# PA-15-30W.net
KiCad netlist of a schematic drawn in Altium Designer
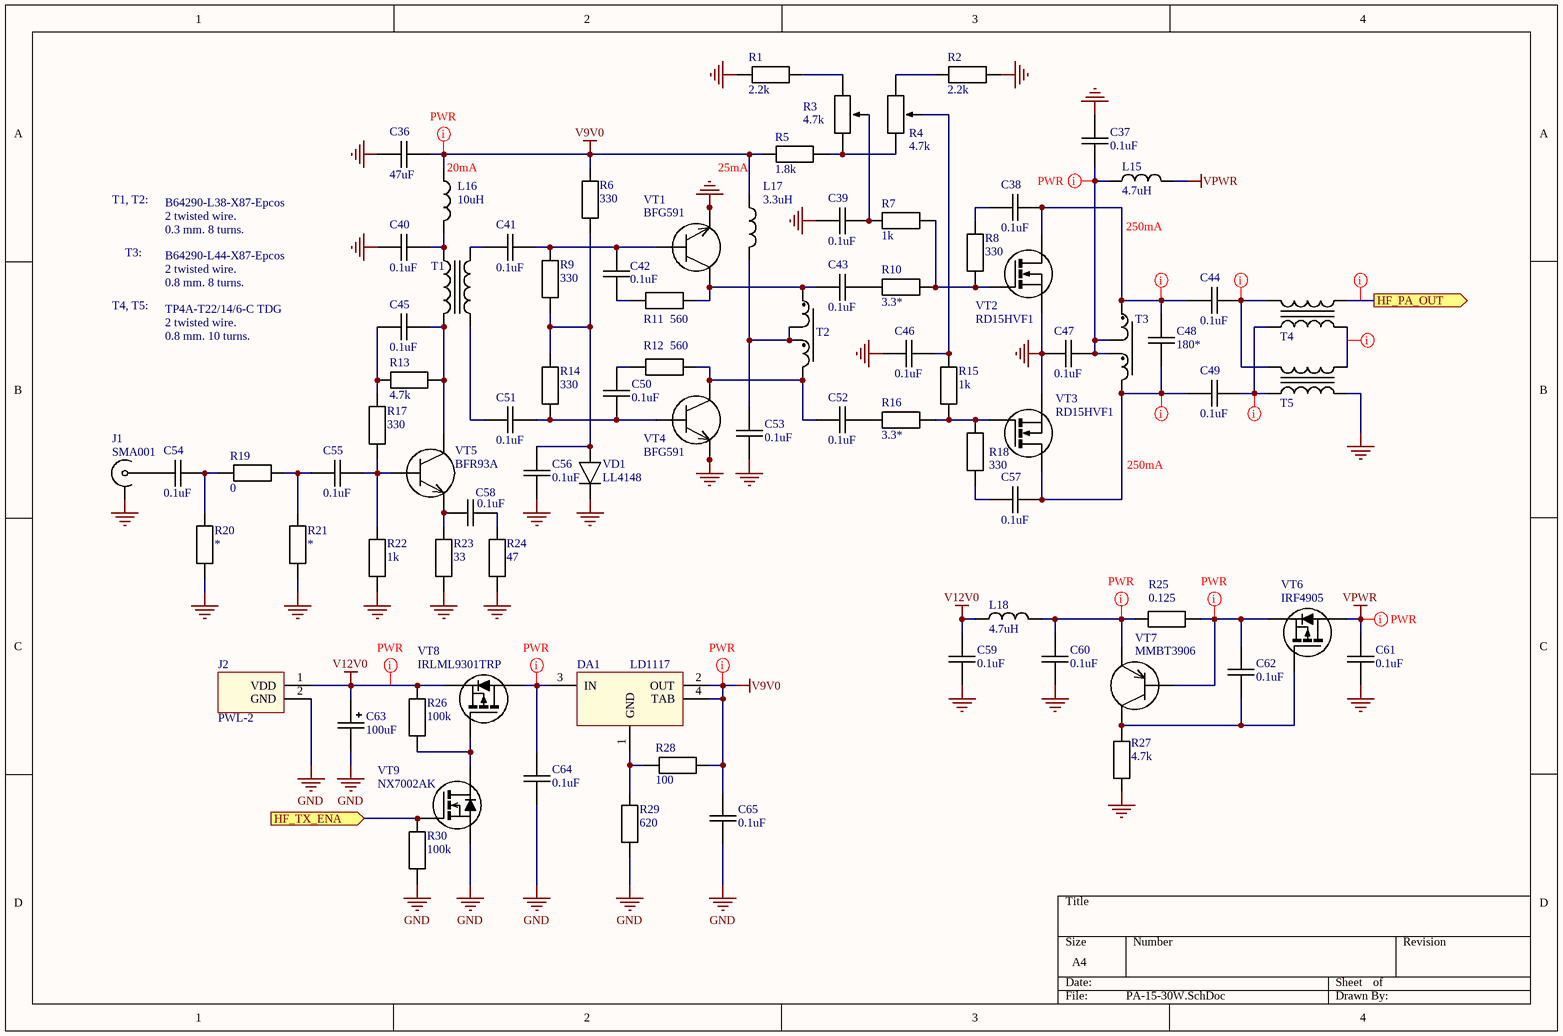
[diagram p0: PA-15-30W.SchDoc]

(export (version "E")
  (design (tool "Eeschema 10.0.6"))
  (components
    (comp (ref "C36")
      (value "47uF")
      (footprint "CAPC3225X270N")
      (description "GRM32ER71A476KE15L")
      (libsource (lib "common-lib") (part "Cap1210"))
    )
    (comp (ref "C37")
      (value "0.1uF")
      (footprint "CAPC3216X125N")
      (description "FM31X104K251EEG")
      (libsource (lib "common-lib") (part "Cap1206"))
    )
    (comp (ref "C38")
      (value "0.1uF")
      (footprint "CAPC2013X100N")
      (description "Capacitor 2x1.25 mm")
      (libsource (lib "common-lib") (part "Cap0805"))
    )
    (comp (ref "C39")
      (value "0.1uF")
      (footprint "CAPC2013X100N")
      (description "Capacitor 2x1.25 mm")
      (libsource (lib "common-lib") (part "Cap0805"))
    )
    (comp (ref "C40")
      (value "0.1uF")
      (footprint "CAPC2013X100N")
      (description "Capacitor 2x1.25 mm")
      (libsource (lib "common-lib") (part "Cap0805"))
    )
    (comp (ref "C41")
      (value "0.1uF")
      (footprint "CAPC2013X100N")
      (description "Capacitor 2x1.25 mm")
      (libsource (lib "common-lib") (part "Cap0805"))
    )
    (comp (ref "C42")
      (value "0.1uF")
      (footprint "CAPC2013X100N")
      (description "Capacitor 2x1.25 mm")
      (libsource (lib "common-lib") (part "Cap0805"))
    )
    (comp (ref "C43")
      (value "0.1uF")
      (footprint "CAPC2013X100N")
      (description "Capacitor 2x1.25 mm")
      (libsource (lib "common-lib") (part "Cap0805"))
    )
    (comp (ref "C44")
      (value "0.1uF")
      (footprint "CAPC4532X218N")
      (description "GRM43DR72J104KW01 (1812, X7R:EIA, 0.1uF, DC630V), rcs")
      (libsource (lib "common-lib") (part "Cap1812"))
    )
    (comp (ref "C45")
      (value "0.1uF")
      (footprint "CAPC2013X100N")
      (description "Capacitor 2x1.25 mm")
      (libsource (lib "common-lib") (part "Cap0805"))
    )
    (comp (ref "C46")
      (value "0.1uF")
      (footprint "CAPC2013X100N")
      (description "Capacitor 2x1.25 mm")
      (libsource (lib "common-lib") (part "Cap0805"))
    )
    (comp (ref "C47")
      (value "0.1uF")
      (footprint "CAPC3216X125N")
      (description "FM31X104K251EEG, rcs")
      (libsource (lib "common-lib") (part "Cap1206"))
    )
    (comp (ref "C48")
      (value "180*")
      (footprint "CAPC3216X125N")
      (description "1206, NP0, 1kV")
      (libsource (lib "common-lib") (part "Cap1206"))
    )
    (comp (ref "C49")
      (value "0.1uF")
      (footprint "CAPC4532X218N")
      (description "GRM43DR72J104KW01 (1812, X7R:EIA, 0.1uF, DC630V), rcs")
      (libsource (lib "common-lib") (part "Cap1812"))
    )
    (comp (ref "C50")
      (value "0.1uF")
      (footprint "CAPC2013X100N")
      (description "Capacitor 2x1.25 mm")
      (libsource (lib "common-lib") (part "Cap0805"))
    )
    (comp (ref "C51")
      (value "0.1uF")
      (footprint "CAPC2013X100N")
      (description "Capacitor 2x1.25 mm")
      (libsource (lib "common-lib") (part "Cap0805"))
    )
    (comp (ref "C52")
      (value "0.1uF")
      (footprint "CAPC2013X100N")
      (description "Capacitor 2x1.25 mm")
      (libsource (lib "common-lib") (part "Cap0805"))
    )
    (comp (ref "C53")
      (value "0.1uF")
      (footprint "CAPC2013X100N")
      (description "Capacitor 2x1.25 mm")
      (libsource (lib "common-lib") (part "Cap0805"))
    )
    (comp (ref "C54")
      (value "0.1uF")
      (footprint "CAPC2013X100N")
      (description "Capacitor 2x1.25 mm")
      (libsource (lib "common-lib") (part "Cap0805"))
    )
    (comp (ref "C55")
      (value "0.1uF")
      (footprint "CAPC2013X100N")
      (description "Capacitor 2x1.25 mm")
      (libsource (lib "common-lib") (part "Cap0805"))
    )
    (comp (ref "C56")
      (value "0.1uF")
      (footprint "CAPC2013X100N")
      (description "Capacitor 2x1.25 mm")
      (libsource (lib "common-lib") (part "Cap0805"))
    )
    (comp (ref "C57")
      (value "0.1uF")
      (footprint "CAPC2013X100N")
      (description "Capacitor 2x1.25 mm")
      (libsource (lib "common-lib") (part "Cap0805"))
    )
    (comp (ref "C58")
      (value "0.1uF")
      (footprint "CAPC2013X100N")
      (description "Capacitor 2x1.25 mm")
      (libsource (lib "common-lib") (part "Cap0805"))
    )
    (comp (ref "C59")
      (value "0.1uF")
      (footprint "CAPC2013X100N")
      (description "Capacitor 2x1.25 mm")
      (libsource (lib "common-lib") (part "Cap0805"))
    )
    (comp (ref "C60")
      (value "0.1uF")
      (footprint "CAPC2013X100N")
      (description "Capacitor 2x1.25 mm")
      (libsource (lib "common-lib") (part "Cap0805"))
    )
    (comp (ref "C61")
      (value "0.1uF")
      (footprint "CAPC2013X100N")
      (description "Capacitor 2x1.25 mm")
      (libsource (lib "common-lib") (part "Cap0805"))
    )
    (comp (ref "C62")
      (value "0.1uF")
      (footprint "CAPC2013X100N")
      (description "Capacitor 2x1.25 mm")
      (libsource (lib "common-lib") (part "Cap0805"))
    )
    (comp (ref "C63")
      (value "100uF")
      (footprint "CAPPR500-1050X1300")
      (description "EEUFR1E471, imrad")
      (libsource (lib "common-lib") (part "CapPolarized"))
    )
    (comp (ref "C64")
      (value "0.1uF")
      (footprint "CAPC2013X100N")
      (description "Capacitor 2x1.25 mm")
      (libsource (lib "common-lib") (part "Cap0805"))
    )
    (comp (ref "C65")
      (value "0.1uF")
      (footprint "CAPC2013X100N")
      (description "Capacitor 2x1.25 mm")
      (libsource (lib "common-lib") (part "Cap0805"))
    )
    (comp (ref "DA1")
      (value "LD1117")
      (footprint "SOT230P700X180-4N")
      (description "Adjustable and fixed low drop positive voltage regulator")
      (libsource (lib "PALib") (part "LD1117"))
    )
    (comp (ref "J1") (value "SMA001") (footprint "SMA002") (libsource (lib "PALib") (part "RF Connector")))
    (comp (ref "J2")
      (value "PWL-2")
      (footprint "PWL-2")
      (libsource (lib "common-lib") (part "PWR_CONNECTOR"))
    )
    (comp (ref "L15")
      (value "4.7uH")
      (footprint "Inductor radial")
      (description "Bochen, 4.7µH±10%, Idc=5.0А, Rdc мax=0.05")
      (libsource (lib "PALib") (part "Inductor"))
    )
    (comp (ref "L16")
      (value "10uH")
      (footprint "RESC2013X64N")
      (description "SMD 0805 50-100mA\r\nLQM21FN100M70L, Imrad")
      (libsource (lib "") (part "Inductor_1"))
    )
    (comp (ref "L17")
      (value "3.3uH")
      (footprint "RES1270-650X250")
      (description "3,3uH ±10% аксиальный дроссель 670mA 0,34Ohm (KLS18-EC36-3R3K-A – KLS)")
      (libsource (lib "") (part "Inductor_1"))
    )
    (comp (ref "L18")
      (value "4.7uH")
      (footprint "Inductor radial")
      (description "Bochen, 4.7µH±10%, Idc=5.0А, Rdc мax=0.05")
      (libsource (lib "PALib") (part "Inductor"))
    )
    (comp (ref "R1")
      (value "2.2k")
      (footprint "RESC2013X64N")
      (libsource (lib "common-lib") (part "Res0805"))
    )
    (comp (ref "R2")
      (value "2.2k")
      (footprint "RESC2013X64N")
      (libsource (lib "common-lib") (part "Res0805"))
    )
    (comp (ref "R3")
      (value "4.7k")
      (footprint "3296W")
      (description "4,7 kOhm 3296W (KLS4-3296W-472), rcs")
      (libsource (lib "PALib") (part "potentiometer"))
    )
    (comp (ref "R4") (value "4.7k") (footprint "3296W") (libsource (lib "PALib") (part "potentiometer")))
    (comp (ref "R5")
      (value "1.8k")
      (footprint "RESC2013X64N")
      (libsource (lib "common-lib") (part "Res0805"))
    )
    (comp (ref "R6") (value "330") (footprint "RESC2013X64N") (libsource (lib "common-lib") (part "Res0805")))
    (comp (ref "R7") (value "1k") (footprint "RESC2013X64N") (libsource (lib "common-lib") (part "Res0805")))
    (comp (ref "R8") (value "330") (footprint "RESC2013X64N") (libsource (lib "common-lib") (part "Res0805")))
    (comp (ref "R9") (value "330") (footprint "RESC2013X64N") (libsource (lib "common-lib") (part "Res0805")))
    (comp (ref "R10")
      (value "3.3*")
      (footprint "RESC2013X64N")
      (libsource (lib "common-lib") (part "Res0805"))
    )
    (comp (ref "R11")
      (value "560")
      (footprint "RESC2013X64N")
      (libsource (lib "common-lib") (part "Res0805"))
    )
    (comp (ref "R12")
      (value "560")
      (footprint "RESC2013X64N")
      (libsource (lib "common-lib") (part "Res0805"))
    )
    (comp (ref "R13")
      (value "4.7k")
      (footprint "RESC2013X64N")
      (libsource (lib "common-lib") (part "Res0805"))
    )
    (comp (ref "R14")
      (value "330")
      (footprint "RESC2013X64N")
      (libsource (lib "common-lib") (part "Res0805"))
    )
    (comp (ref "R15") (value "1k") (footprint "RESC2013X64N") (libsource (lib "common-lib") (part "Res0805")))
    (comp (ref "R16")
      (value "3.3*")
      (footprint "RESC2013X64N")
      (libsource (lib "common-lib") (part "Res0805"))
    )
    (comp (ref "R17")
      (value "330")
      (footprint "RESC2013X64N")
      (libsource (lib "common-lib") (part "Res0805"))
    )
    (comp (ref "R18")
      (value "330")
      (footprint "RESC2013X64N")
      (libsource (lib "common-lib") (part "Res0805"))
    )
    (comp (ref "R19") (value "0") (footprint "RESC2013X64N") (libsource (lib "common-lib") (part "Res0805")))
    (comp (ref "R20") (value "*") (footprint "RESC2013X64N") (libsource (lib "common-lib") (part "Res0805")))
    (comp (ref "R21") (value "*") (footprint "RESC2013X64N") (libsource (lib "common-lib") (part "Res0805")))
    (comp (ref "R22") (value "1k") (footprint "RESC2013X64N") (libsource (lib "common-lib") (part "Res0805")))
    (comp (ref "R23") (value "33") (footprint "RESC2013X64N") (libsource (lib "common-lib") (part "Res0805")))
    (comp (ref "R24") (value "47") (footprint "RESC2013X64N") (libsource (lib "common-lib") (part "Res0805")))
    (comp (ref "R25")
      (value "0.125")
      (footprint "RESC3216X80N")
      (description "8 items 1 Om in paralel,1206")
      (libsource (lib "common-lib") (part "Res0805"))
    )
    (comp (ref "R26")
      (value "100k")
      (footprint "RESC2013X64N")
      (libsource (lib "common-lib") (part "Res0805"))
    )
    (comp (ref "R27")
      (value "4.7k")
      (footprint "RESC2013X64N")
      (libsource (lib "common-lib") (part "Res0805"))
    )
    (comp (ref "R28")
      (value "100")
      (footprint "RESC2013X64N")
      (libsource (lib "common-lib") (part "Res0805"))
    )
    (comp (ref "R29")
      (value "620")
      (footprint "RESC2013X64N")
      (libsource (lib "common-lib") (part "Res0805"))
    )
    (comp (ref "R30")
      (value "100k")
      (footprint "RESC2013X64N")
      (libsource (lib "common-lib") (part "Res0805"))
    )
    (comp (ref "T1")
      (value "R10*6*4 N87")
      (footprint "R10x6x4")
      (description "R10*6*4 N87 (В64290-L38-Х87-Epcos)")
      (libsource (lib "") (part "transformer type 2_1"))
    )
    (comp (ref "T2")
      (value "R10*6*4 N87")
      (footprint "R10x6x4")
      (description "R10*6*4 N87 (В64290-L38-Х87-Epcos)")
      (libsource (lib "PALib") (part "transformer type 1"))
    )
    (comp (ref "T3")
      (value "R12,5*7,5*5 N87")
      (footprint "R12.5x7.5x5")
      (description "R12,5*7,5*5 N87 (B64290-L44-X87-Epcos)")
      (libsource (lib "PALib") (part "transformer type 1"))
    )
    (comp (ref "T4")
      (value "TP4A-T22/14/6-C TDG")
      (footprint "R22x14x6")
      (libsource (lib "PALib") (part "transformer type 2"))
    )
    (comp (ref "T5")
      (value "TP4A-T22/14/6-C TDG")
      (footprint "R22x14x6")
      (libsource (lib "PALib") (part "transformer type 2"))
    )
    (comp (ref "VD1") (value "LL4148") (footprint "DIOMELF3515N") (libsource (lib "PALib") (part "DIODE")))
    (comp (ref "VT1")
      (value "BFG591")
      (footprint "SOT230P700X180-4N")
      (description "NPN 7 GHz wideband transistor")
      (libsource (lib "PALib") (part "BFG591"))
    )
    (comp (ref "VT2")
      (value "RD15HVF1")
      (footprint "TO-220-HFLIP")
      (libsource (lib "PALib") (part "RD15HVF1"))
    )
    (comp (ref "VT3") (value "RD15HVF1") (footprint "TO-220-HFLIP") (libsource (lib "") (part "RD15HVF1_1")))
    (comp (ref "VT4")
      (value "BFG591")
      (footprint "SOT230P700X180-4N")
      (description "NPN 7 GHz wideband transistor")
      (libsource (lib "PALib") (part "BFG591"))
    )
    (comp (ref "VT5")
      (value "BFR93A")
      (footprint "SOT95P229X119-3N")
      (description "NPN 6 GHz wideband transistor")
      (libsource (lib "PALib") (part "BFR93A"))
    )
    (comp (ref "VT6")
      (value "IRF4905")
      (footprint "TO-220-v")
      (description "HEXFET® Power MOSFET")
      (libsource (lib "PALib") (part "IRF4905"))
    )
    (comp (ref "VT7")
      (value "MMBT3906")
      (footprint "SOT95P229X119-3N")
      (description "MMBT3906LT1G, PNP General Purpose Amplifier\r\nimrad")
      (libsource (lib "PALib") (part "MMBT3906"))
    )
    (comp (ref "VT8")
      (value "IRLML9301TRP")
      (footprint "SOT95P229X119-3N")
      (libsource (lib "PALib") (part "IRLML9301TRP"))
    )
    (comp (ref "VT9")
      (value "NX7002AK")
      (footprint "SOT95P229X119-3N")
      (libsource (lib "common-lib") (part "N-MOSFET 1G 2S 3D"))
    )
  )
  (nets
    (net (code "1") (name "/HF_PA_OUT") (class "Default") (node (ref "T4") (pin "4") (pintype "passive")))
    (net (code "2") (name "/HF_TX_ENA") (class "Default")
      (node (ref "R30") (pin "2") (pintype "passive"))
      (node (ref "VT9") (pin "1") (pinfunction "G_1") (pintype "passive"))
    )
    (net (code "3") (name "GND") (class "Default")
      (node (ref "C36") (pin "1") (pintype "passive"))
      (node (ref "C37") (pin "2") (pintype "passive"))
      (node (ref "C39") (pin "2") (pintype "passive"))
      (node (ref "C40") (pin "2") (pintype "passive"))
      (node (ref "C46") (pin "1") (pintype "passive"))
      (node (ref "C47") (pin "1") (pintype "passive"))
      (node (ref "C53") (pin "2") (pintype "passive"))
      (node (ref "C56") (pin "2") (pintype "passive"))
      (node (ref "C59") (pin "2") (pintype "passive"))
      (node (ref "C60") (pin "2") (pintype "passive"))
      (node (ref "C61") (pin "2") (pintype "passive"))
      (node (ref "C63") (pin "2") (pintype "passive"))
      (node (ref "C64") (pin "1") (pintype "passive"))
      (node (ref "C65") (pin "1") (pintype "passive"))
      (node (ref "J1") (pin "2") (pinfunction "GND_2") (pintype "passive"))
      (node (ref "J2") (pin "2") (pinfunction "GND_2") (pintype "power_in"))
      (node (ref "R1") (pin "1") (pintype "passive"))
      (node (ref "R2") (pin "1") (pintype "passive"))
      (node (ref "R20") (pin "1") (pintype "passive"))
      (node (ref "R21") (pin "1") (pintype "passive"))
      (node (ref "R22") (pin "1") (pintype "passive"))
      (node (ref "R23") (pin "1") (pintype "passive"))
      (node (ref "R24") (pin "1") (pintype "passive"))
      (node (ref "R27") (pin "2") (pintype "passive"))
      (node (ref "R29") (pin "1") (pintype "passive"))
      (node (ref "R30") (pin "1") (pintype "passive"))
      (node (ref "T5") (pin "3") (pintype "passive"))
      (node (ref "VD1") (pin "1") (pinfunction "C_1") (pintype "passive"))
      (node (ref "VT1") (pin "1") (pinfunction "E_1") (pintype "passive"))
      (node (ref "VT1") (pin "3") (pinfunction "E_3") (pintype "passive"))
      (node (ref "VT2") (pin "2") (pinfunction "S_2") (pintype "passive"))
      (node (ref "VT3") (pin "2") (pinfunction "S_2") (pintype "passive"))
      (node (ref "VT4") (pin "1") (pinfunction "E_1") (pintype "passive"))
      (node (ref "VT4") (pin "3") (pinfunction "E_3") (pintype "passive"))
      (node (ref "VT9") (pin "2") (pinfunction "S_2") (pintype "passive"))
    )
    (net (code "4") (name "Net-(C37-Pad1)") (class "Default")
      (node (ref "C37") (pin "1") (pintype "passive"))
      (node (ref "C47") (pin "2") (pintype "passive"))
      (node (ref "L15") (pin "1") (pintype "passive"))
      (node (ref "T3") (pin "2") (pintype "passive"))
      (node (ref "T3") (pin "4") (pintype "passive"))
    )
    (net (code "5") (name "Net-(C38-Pad2)") (class "Default")
      (node (ref "C38") (pin "2") (pintype "passive"))
      (node (ref "R8") (pin "2") (pintype "passive"))
    )
    (net (code "6") (name "Net-(C39-Pad1)") (class "Default")
      (node (ref "C39") (pin "1") (pintype "passive"))
      (node (ref "R3") (pin "2") (pintype "passive"))
      (node (ref "R7") (pin "2") (pintype "passive"))
    )
    (net (code "7") (name "Net-(C40-Pad1)") (class "Default")
      (node (ref "C40") (pin "1") (pintype "passive"))
      (node (ref "L16") (pin "1") (pintype "passive"))
      (node (ref "T1") (pin "1") (pintype "passive"))
    )
    (net (code "8") (name "Net-(C41-Pad2)") (class "Default")
      (node (ref "C41") (pin "2") (pintype "passive"))
      (node (ref "T1") (pin "2") (pintype "passive"))
    )
    (net (code "9") (name "Net-(C42-Pad1)") (class "Default")
      (node (ref "C42") (pin "1") (pintype "passive"))
      (node (ref "R11") (pin "1") (pintype "passive"))
    )
    (net (code "10") (name "Net-(C43-Pad1)") (class "Default")
      (node (ref "C43") (pin "1") (pintype "passive"))
      (node (ref "R10") (pin "2") (pintype "passive"))
    )
    (net (code "11") (name "Net-(C44-Pad2)") (class "Default")
      (node (ref "C44") (pin "2") (pintype "passive"))
      (node (ref "T4") (pin "1") (pintype "passive"))
      (node (ref "T5") (pin "1") (pintype "passive"))
    )
    (net (code "12") (name "Net-(C45-Pad2)") (class "Default")
      (node (ref "C45") (pin "2") (pintype "passive"))
      (node (ref "R13") (pin "2") (pintype "passive"))
      (node (ref "R17") (pin "2") (pintype "passive"))
    )
    (net (code "13") (name "Net-(C46-Pad2)") (class "Default")
      (node (ref "C46") (pin "2") (pintype "passive"))
      (node (ref "R15") (pin "2") (pintype "passive"))
      (node (ref "R4") (pin "2") (pintype "passive"))
    )
    (net (code "14") (name "Net-(C49-Pad2)") (class "Default")
      (node (ref "C49") (pin "2") (pintype "passive"))
      (node (ref "T4") (pin "2") (pintype "passive"))
      (node (ref "T5") (pin "2") (pintype "passive"))
    )
    (net (code "15") (name "Net-(C50-Pad2)") (class "Default")
      (node (ref "C50") (pin "2") (pintype "passive"))
      (node (ref "R12") (pin "1") (pintype "passive"))
    )
    (net (code "16") (name "Net-(C51-Pad2)") (class "Default")
      (node (ref "C51") (pin "2") (pintype "passive"))
      (node (ref "T1") (pin "3") (pintype "passive"))
    )
    (net (code "17") (name "Net-(C52-Pad1)") (class "Default")
      (node (ref "C52") (pin "1") (pintype "passive"))
      (node (ref "R16") (pin "2") (pintype "passive"))
    )
    (net (code "18") (name "Net-(C53-Pad1)") (class "Default")
      (node (ref "C53") (pin "1") (pintype "passive"))
      (node (ref "L17") (pin "1") (pintype "passive"))
      (node (ref "T2") (pin "2") (pintype "passive"))
      (node (ref "T2") (pin "4") (pintype "passive"))
    )
    (net (code "19") (name "Net-(C54-Pad2)") (class "Default")
      (node (ref "C54") (pin "2") (pintype "passive"))
      (node (ref "R19") (pin "1") (pintype "passive"))
      (node (ref "R20") (pin "2") (pintype "passive"))
    )
    (net (code "20") (name "Net-(C55-Pad1)") (class "Default")
      (node (ref "C55") (pin "1") (pintype "passive"))
      (node (ref "R19") (pin "2") (pintype "passive"))
      (node (ref "R21") (pin "2") (pintype "passive"))
    )
    (net (code "21") (name "Net-(C57-Pad2)") (class "Default")
      (node (ref "C57") (pin "2") (pintype "passive"))
      (node (ref "R18") (pin "1") (pintype "passive"))
    )
    (net (code "22") (name "Net-(C58-Pad1)") (class "Default")
      (node (ref "C58") (pin "1") (pintype "passive"))
      (node (ref "R24") (pin "2") (pintype "passive"))
    )
    (net (code "23") (name "Net-(DA1-GND)") (class "Default")
      (node (ref "DA1") (pin "1") (pinfunction "GND_1") (pintype "passive"))
      (node (ref "R28") (pin "1") (pintype "passive"))
      (node (ref "R29") (pin "2") (pintype "passive"))
    )
    (net (code "24") (name "Net-(DA1-IN)") (class "Default")
      (node (ref "C64") (pin "2") (pintype "passive"))
      (node (ref "DA1") (pin "3") (pinfunction "IN_3") (pintype "passive"))
      (node (ref "VT8") (pin "3") (pinfunction "D_3") (pintype "passive"))
    )
    (net (code "25") (name "Net-(J1-RF)") (class "Default")
      (node (ref "C54") (pin "1") (pintype "passive"))
      (node (ref "J1") (pin "1") (pinfunction "RF_1") (pintype "passive"))
    )
    (net (code "26") (name "Net-(R1-Pad2)") (class "Default")
      (node (ref "R1") (pin "2") (pintype "passive"))
      (node (ref "R3") (pin "3") (pintype "passive"))
    )
    (net (code "27") (name "Net-(R2-Pad2)") (class "Default")
      (node (ref "R2") (pin "2") (pintype "passive"))
      (node (ref "R4") (pin "3") (pintype "passive"))
    )
    (net (code "28") (name "Net-(R3-Pad1)") (class "Default")
      (node (ref "R3") (pin "1") (pintype "passive"))
      (node (ref "R4") (pin "1") (pintype "passive"))
      (node (ref "R5") (pin "1") (pintype "passive"))
    )
    (net (code "29") (name "Net-(T4-Pad3)") (class "Default")
      (node (ref "T4") (pin "3") (pintype "passive"))
      (node (ref "T5") (pin "4") (pintype "passive"))
    )
    (net (code "30") (name "Net-(VD1-A)") (class "Default")
      (node (ref "C56") (pin "1") (pintype "passive"))
      (node (ref "R14") (pin "2") (pintype "passive"))
      (node (ref "R6") (pin "1") (pintype "passive"))
      (node (ref "R9") (pin "1") (pintype "passive"))
      (node (ref "VD1") (pin "2") (pinfunction "A_2") (pintype "passive"))
    )
    (net (code "31") (name "Net-(VT1-B)") (class "Default")
      (node (ref "C41") (pin "1") (pintype "passive"))
      (node (ref "C42") (pin "2") (pintype "passive"))
      (node (ref "R9") (pin "2") (pintype "passive"))
      (node (ref "VT1") (pin "2") (pinfunction "B_2") (pintype "passive"))
    )
    (net (code "32") (name "Net-(VT1-C)") (class "Default")
      (node (ref "C43") (pin "2") (pintype "passive"))
      (node (ref "R11") (pin "2") (pintype "passive"))
      (node (ref "T2") (pin "3") (pintype "passive"))
      (node (ref "VT1") (pin "4") (pinfunction "C_4") (pintype "passive"))
    )
    (net (code "33") (name "Net-(VT2-D)") (class "Default")
      (node (ref "C38") (pin "1") (pintype "passive"))
      (node (ref "C44") (pin "1") (pintype "passive"))
      (node (ref "C48") (pin "2") (pintype "passive"))
      (node (ref "T3") (pin "3") (pintype "passive"))
      (node (ref "VT2") (pin "3") (pinfunction "D_3") (pintype "passive"))
    )
    (net (code "34") (name "Net-(VT2-G)") (class "Default")
      (node (ref "R10") (pin "1") (pintype "passive"))
      (node (ref "R7") (pin "1") (pintype "passive"))
      (node (ref "R8") (pin "1") (pintype "passive"))
      (node (ref "VT2") (pin "1") (pinfunction "G_1") (pintype "passive"))
    )
    (net (code "35") (name "Net-(VT3-D)") (class "Default")
      (node (ref "C48") (pin "1") (pintype "passive"))
      (node (ref "C49") (pin "1") (pintype "passive"))
      (node (ref "C57") (pin "1") (pintype "passive"))
      (node (ref "T3") (pin "1") (pintype "passive"))
      (node (ref "VT3") (pin "3") (pinfunction "D_3") (pintype "passive"))
    )
    (net (code "36") (name "Net-(VT3-G)") (class "Default")
      (node (ref "R15") (pin "1") (pintype "passive"))
      (node (ref "R16") (pin "1") (pintype "passive"))
      (node (ref "R18") (pin "2") (pintype "passive"))
      (node (ref "VT3") (pin "1") (pinfunction "G_1") (pintype "passive"))
    )
    (net (code "37") (name "Net-(VT4-B)") (class "Default")
      (node (ref "C50") (pin "1") (pintype "passive"))
      (node (ref "C51") (pin "1") (pintype "passive"))
      (node (ref "R14") (pin "1") (pintype "passive"))
      (node (ref "VT4") (pin "2") (pinfunction "B_2") (pintype "passive"))
    )
    (net (code "38") (name "Net-(VT4-C)") (class "Default")
      (node (ref "C52") (pin "2") (pintype "passive"))
      (node (ref "R12") (pin "2") (pintype "passive"))
      (node (ref "T2") (pin "1") (pintype "passive"))
      (node (ref "VT4") (pin "4") (pinfunction "C_4") (pintype "passive"))
    )
    (net (code "39") (name "Net-(VT5-B)") (class "Default")
      (node (ref "C55") (pin "2") (pintype "passive"))
      (node (ref "R17") (pin "1") (pintype "passive"))
      (node (ref "R22") (pin "2") (pintype "passive"))
      (node (ref "VT5") (pin "1") (pinfunction "B_1") (pintype "passive"))
    )
    (net (code "40") (name "Net-(VT5-C)") (class "Default")
      (node (ref "C45") (pin "1") (pintype "passive"))
      (node (ref "R13") (pin "1") (pintype "passive"))
      (node (ref "T1") (pin "4") (pintype "passive"))
      (node (ref "VT5") (pin "3") (pinfunction "C_3") (pintype "passive"))
    )
    (net (code "41") (name "Net-(VT5-E)") (class "Default")
      (node (ref "C58") (pin "2") (pintype "passive"))
      (node (ref "R23") (pin "2") (pintype "passive"))
      (node (ref "VT5") (pin "2") (pinfunction "E_2") (pintype "passive"))
    )
    (net (code "42") (name "Net-(VT6-G)") (class "Default")
      (node (ref "C62") (pin "2") (pintype "passive"))
      (node (ref "R27") (pin "1") (pintype "passive"))
      (node (ref "VT6") (pin "1") (pinfunction "G_1") (pintype "passive"))
      (node (ref "VT7") (pin "3") (pinfunction "C_3") (pintype "passive"))
    )
    (net (code "43") (name "Net-(VT6-S)") (class "Default")
      (node (ref "C62") (pin "1") (pintype "passive"))
      (node (ref "R25") (pin "1") (pintype "passive"))
      (node (ref "VT6") (pin "3") (pinfunction "S_3") (pintype "passive"))
      (node (ref "VT7") (pin "1") (pinfunction "B_1") (pintype "passive"))
    )
    (net (code "44") (name "Net-(VT7-E)") (class "Default")
      (node (ref "C60") (pin "1") (pintype "passive"))
      (node (ref "L18") (pin "2") (pintype "passive"))
      (node (ref "R25") (pin "2") (pintype "passive"))
      (node (ref "VT7") (pin "2") (pinfunction "E_2") (pintype "passive"))
    )
    (net (code "45") (name "Net-(VT8-G)") (class "Default")
      (node (ref "R26") (pin "1") (pintype "passive"))
      (node (ref "VT8") (pin "1") (pinfunction "G_1") (pintype "passive"))
      (node (ref "VT9") (pin "3") (pinfunction "D_3") (pintype "passive"))
    )
    (net (code "46") (name "V9V0") (class "Default")
      (node (ref "C36") (pin "2") (pintype "passive"))
      (node (ref "C65") (pin "2") (pintype "passive"))
      (node (ref "DA1") (pin "2") (pinfunction "OUT_2") (pintype "passive"))
      (node (ref "DA1") (pin "4") (pinfunction "TAB_4") (pintype "passive"))
      (node (ref "L16") (pin "2") (pintype "passive"))
      (node (ref "L17") (pin "2") (pintype "passive"))
      (node (ref "R28") (pin "2") (pintype "passive"))
      (node (ref "R5") (pin "2") (pintype "passive"))
      (node (ref "R6") (pin "2") (pintype "passive"))
    )
    (net (code "47") (name "V12V0") (class "Default")
      (node (ref "C59") (pin "1") (pintype "passive"))
      (node (ref "C63") (pin "1") (pintype "passive"))
      (node (ref "J2") (pin "1") (pinfunction "VDD_1") (pintype "power_in"))
      (node (ref "L18") (pin "1") (pintype "passive"))
      (node (ref "R26") (pin "2") (pintype "passive"))
      (node (ref "VT8") (pin "2") (pinfunction "S_2") (pintype "passive"))
    )
    (net (code "48") (name "VPWR") (class "Default")
      (node (ref "C61") (pin "1") (pintype "passive"))
      (node (ref "L15") (pin "2") (pintype "passive"))
      (node (ref "VT6") (pin "2") (pinfunction "D_2") (pintype "passive"))
    )
  )
)
